# input_filter.net
KiCad netlist of a schematic drawn in Altium Designer
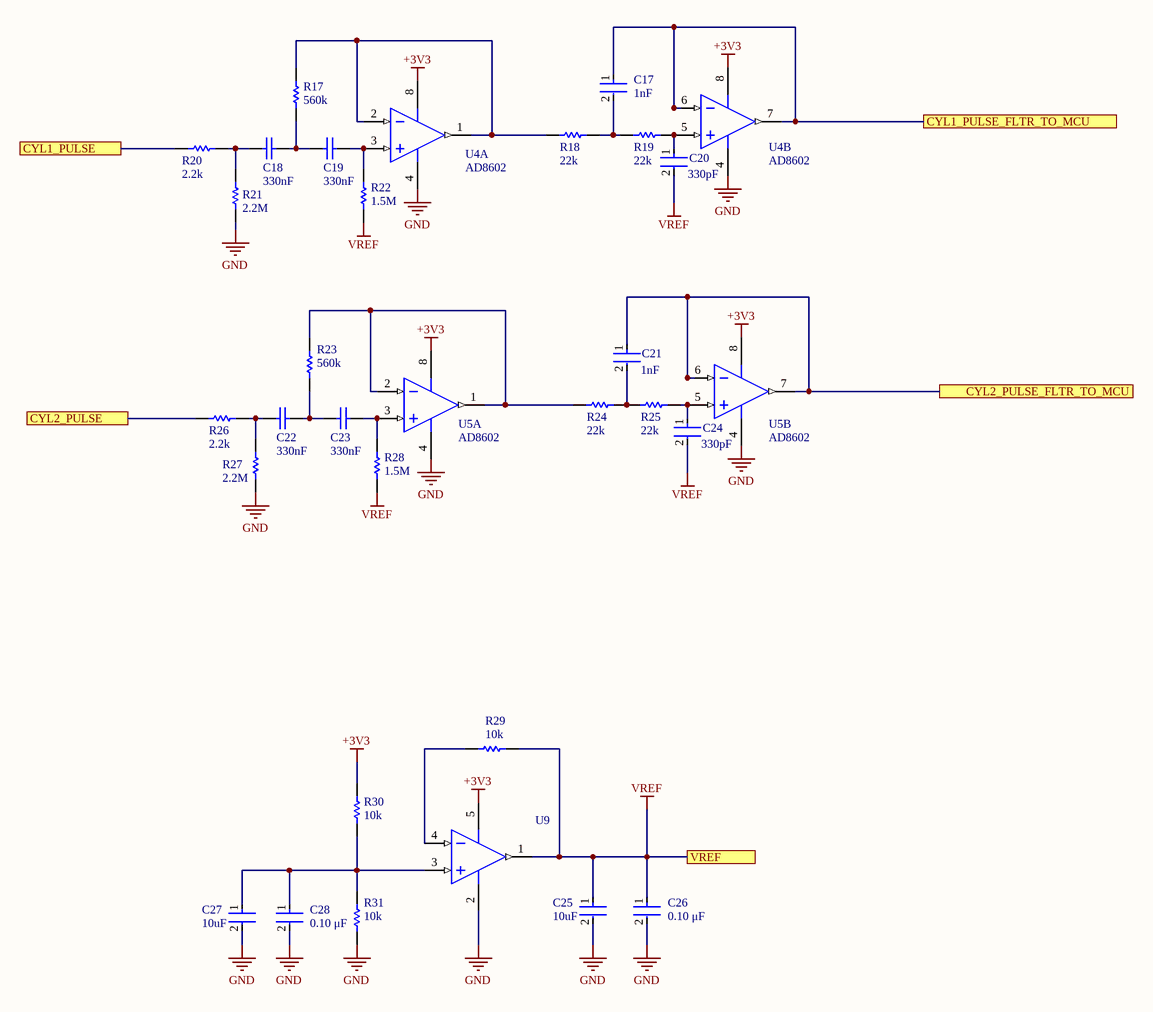
[diagram p0: input_filter.SchDoc]

(export (version "E")
  (design (tool "Eeschema 10.0.6"))
  (components
    (comp (ref "C17")
      (value "GRM1555C1H102JA01D")
      (footprint "FP-GRM155-0_05-IPC_B")
      (description "Chip Multilayer Ceramic Capacitors for General Purpose, 0402, 1000pF, C0G, 30ppm/°C, 5%, 50V")
      (fields
        (field (name "TOLERANCE") "5%")
        (field (name "VOLTAGE") "50V")
        (field (name "CAPACITANCE") "1nF")
      )
      (libsource (lib "Altium Content Vault") (part "02cd4be3c70576c341d710602a673aa"))
    )
    (comp (ref "C18")
      (value "330nF")
      (footprint "CAPC1005X55X25ML05T10")
      (fields (field (name "PART NUMBER") "GRM155R61A334KE15D") (field (name "MANUFACTURER") "Murata"))
      (libsource (lib "Altium Content Vault") (part "CAP"))
    )
    (comp (ref "C19")
      (value "330nF")
      (footprint "CAPC1005X55X25ML05T10")
      (fields (field (name "PART NUMBER") "GRM155R61A334KE15D") (field (name "MANUFACTURER") "Murata"))
      (libsource (lib "Altium Content Vault") (part "CAP"))
    )
    (comp (ref "C20")
      (value "GRM1555C1H331JA01D")
      (footprint "FP-GRM155-0_05-MFG")
      (description "Chip Multilayer Ceramic Capacitors for General Purpose, 0402, 330pF, C0G, 30ppm/°C, 5%, 50V")
      (fields
        (field (name "TOLERANCE") "5%")
        (field (name "VOLTAGE") "50V")
        (field (name "CAPACITANCE") "330pF")
      )
      (libsource (lib "Altium Content Vault") (part "02cd4be3c70576c341d710602a673aa"))
    )
    (comp (ref "C21")
      (value "GRM1555C1H102JA01D")
      (footprint "FP-GRM155-0_05-IPC_B")
      (description "Chip Multilayer Ceramic Capacitors for General Purpose, 0402, 1000pF, C0G, 30ppm/°C, 5%, 50V")
      (fields
        (field (name "TOLERANCE") "5%")
        (field (name "VOLTAGE") "50V")
        (field (name "CAPACITANCE") "1nF")
      )
      (libsource (lib "Altium Content Vault") (part "02cd4be3c70576c341d710602a673aa"))
    )
    (comp (ref "C22")
      (value "330nF")
      (footprint "CAPC1005X55X25ML05T10")
      (fields (field (name "PART NUMBER") "GRM155R61A334KE15D") (field (name "MANUFACTURER") "Murata"))
      (libsource (lib "Altium Content Vault") (part "CAP"))
    )
    (comp (ref "C23")
      (value "330nF")
      (footprint "CAPC1005X55X25ML05T10")
      (fields (field (name "PART NUMBER") "GRM155R61A334KE15D") (field (name "MANUFACTURER") "Murata"))
      (libsource (lib "Altium Content Vault") (part "CAP"))
    )
    (comp (ref "C24")
      (value "GRM1555C1H331JA01D")
      (footprint "FP-GRM155-0_05-MFG")
      (description "Chip Multilayer Ceramic Capacitors for General Purpose, 0402, 330pF, C0G, 30ppm/°C, 5%, 50V")
      (fields
        (field (name "TOLERANCE") "5%")
        (field (name "VOLTAGE") "50V")
        (field (name "CAPACITANCE") "330pF")
      )
      (libsource (lib "Altium Content Vault") (part "02cd4be3c70576c341d710602a673aa"))
    )
    (comp (ref "C25")
      (value "CL05A106MP5NUNC")
      (footprint "FP-CL05A106MP5NUNC-MFG")
      (description "CAP CER 10UF 10V X5R 0402")
      (fields
        (field (name "OCTOPART") "https://octopart.com/cl05a106mp5nunc-samsung-22457395")
        (field (name "TOLERANCE") "20%")
        (field (name "CAPACITANCE") "10uF")
      )
      (libsource (lib "Altium Content Vault") (part "b4654b650e69147ec39a6b967a45e02"))
    )
    (comp (ref "C26")
      (value "C0402C104K8PACTU")
      (footprint "FP-C0402-BB-MFG")
      (description "CAP CER 0.1UF 10V X5R 0402")
      (fields
        (field (name "CAPACITANCE") "0.10 μF")
        (field (name "MANUFACTURER") "Kemet")
        (field (name "TOLERANCE") "0.1")
      )
      (libsource (lib "Altium Content Vault") (part "b4654b650e69147ec39a6b967a45e02"))
    )
    (comp (ref "C27")
      (value "CL05A106MP5NUNC")
      (footprint "FP-CL05A106MP5NUNC-MFG")
      (description "CAP CER 10UF 10V X5R 0402")
      (fields
        (field (name "OCTOPART") "https://octopart.com/cl05a106mp5nunc-samsung-22457395")
        (field (name "TOLERANCE") "20%")
        (field (name "CAPACITANCE") "10uF")
      )
      (libsource (lib "Altium Content Vault") (part "b4654b650e69147ec39a6b967a45e02"))
    )
    (comp (ref "C28")
      (value "0.10 μF")
      (footprint "FP-C0402-BB-MFG")
      (description "CAP CER 0.1UF 10V X5R 0402")
      (fields (field (name "MANUFACTURER") "Kemet") (field (name "TOLERANCE") "0.1"))
      (libsource (lib "Altium Content Vault") (part "b4654b650e69147ec39a6b967a45e02"))
    )
    (comp (ref "R17")
      (value "560k")
      (footprint "RESC1005X40X25LL05T10")
      (fields (field (name "PART NUMBER") "RC0402FR-07560KL") (field (name "MANUFACTURER") "Yageo / Phycomp"))
      (libsource (lib "Altium Content Vault") (part "RES"))
    )
    (comp (ref "R18")
      (value "22k")
      (footprint "RESC1005X40X25NL05T10")
      (fields (field (name "MANUFACTURER") "Yageo / Phycomp") (field (name "PART NUMBER") "RC0402FR-0722KL"))
      (libsource (lib "Altium Content Vault") (part "RES"))
    )
    (comp (ref "R19")
      (value "22k")
      (footprint "RESC1005X40X25NL05T10")
      (fields (field (name "MANUFACTURER") "Yageo / Phycomp") (field (name "PART NUMBER") "RC0402FR-0722KL"))
      (libsource (lib "Altium Content Vault") (part "RES"))
    )
    (comp (ref "R20")
      (value "2.2k")
      (footprint "RESC1005X40X25NL05T10")
      (fields (field (name "MANUFACTURER") "Yageo / Phycomp") (field (name "PART NUMBER") "RC0402FR-0722KL"))
      (libsource (lib "Altium Content Vault") (part "RES"))
    )
    (comp (ref "R21")
      (value "2.2M")
      (footprint "RESC1005X40X25ML05T10")
      (fields (field (name "PART NUMBER") "RC0402FR-072M2L") (field (name "MANUFACTURER") "Yageo / Phycomp"))
      (libsource (lib "Altium Content Vault") (part "RES"))
    )
    (comp (ref "R22")
      (value "1.5M")
      (footprint "RESC1005X40X25NL05T10")
      (fields (field (name "MANUFACTURER") "Yageo / Phycomp") (field (name "PART NUMBER") "RC0402FR-071M5L"))
      (libsource (lib "Altium Content Vault") (part "RES"))
    )
    (comp (ref "R23")
      (value "560k")
      (footprint "RESC1005X40X25LL05T10")
      (fields (field (name "PART NUMBER") "RC0402FR-07560KL") (field (name "MANUFACTURER") "Yageo / Phycomp"))
      (libsource (lib "Altium Content Vault") (part "RES"))
    )
    (comp (ref "R24")
      (value "22k")
      (footprint "RESC1005X40X25NL05T10")
      (fields (field (name "MANUFACTURER") "Yageo / Phycomp") (field (name "PART NUMBER") "RC0402FR-0722KL"))
      (libsource (lib "Altium Content Vault") (part "RES"))
    )
    (comp (ref "R25")
      (value "22k")
      (footprint "RESC1005X40X25NL05T10")
      (fields (field (name "MANUFACTURER") "Yageo / Phycomp") (field (name "PART NUMBER") "RC0402FR-0722KL"))
      (libsource (lib "Altium Content Vault") (part "RES"))
    )
    (comp (ref "R26")
      (value "2.2k")
      (footprint "RESC1005X40X25NL05T10")
      (fields (field (name "MANUFACTURER") "Yageo / Phycomp") (field (name "PART NUMBER") "RC0402FR-0722KL"))
      (libsource (lib "Altium Content Vault") (part "RES"))
    )
    (comp (ref "R27")
      (value "2.2M")
      (footprint "RESC1005X40X25ML05T10")
      (fields (field (name "PART NUMBER") "RC0402FR-072M2L") (field (name "MANUFACTURER") "Yageo / Phycomp"))
      (libsource (lib "Altium Content Vault") (part "RES"))
    )
    (comp (ref "R28")
      (value "1.5M")
      (footprint "RESC1005X40X25NL05T10")
      (fields (field (name "MANUFACTURER") "Yageo / Phycomp") (field (name "PART NUMBER") "RC0402FR-071M5L"))
      (libsource (lib "Altium Content Vault") (part "RES"))
    )
    (comp (ref "R29")
      (value "10k")
      (footprint "RESC1005X40X25LL05T10")
      (fields (field (name "PART NUMBER") "RC0402FR-0710KL") (field (name "MANUFACTURER") "Yageo / Phycomp"))
      (libsource (lib "Altium Content Vault") (part "RES"))
    )
    (comp (ref "R30")
      (value "10k")
      (footprint "RESC1005X40X25LL05T10")
      (fields (field (name "PART NUMBER") "RC0402FR-0710KL") (field (name "MANUFACTURER") "Yageo / Phycomp"))
      (libsource (lib "Altium Content Vault") (part "RES"))
    )
    (comp (ref "R31")
      (value "10k")
      (footprint "RESC1005X40X25LL05T10")
      (fields (field (name "PART NUMBER") "RC0402FR-0710KL") (field (name "MANUFACTURER") "Yageo / Phycomp"))
      (libsource (lib "Altium Content Vault") (part "RES"))
    )
    (comp (ref "U4")
      (value "AD8602DRM-REEL")
      (footprint "ADI-RM-8_M")
      (fields (field (name "MANUFACTURER") "Analog Devices") (field (name "GENERIC PART NUMBER") "AD8602"))
      (libsource (lib "Altium Content Vault") (part "ADI-OP29X-R-8"))
    )
    (comp (ref "U5")
      (value "AD8602DRM-REEL")
      (footprint "ADI-RM-8_M")
      (fields (field (name "MANUFACTURER") "Analog Devices") (field (name "GENERIC PART NUMBER") "AD8602"))
      (libsource (lib "Altium Content Vault") (part "ADI-OP29X-R-8"))
    )
    (comp (ref "U9")
      (value "AD8031ARTZ-REEL7")
      (footprint "ADI-RJ-5_L")
      (fields (field (name "MANUFACTURER") "Analog Devices") (field (name "GENERIC PART NUMBER") "AD8031"))
      (libsource (lib "Altium Content Vault") (part "ADI-AD80XX-5"))
    )
  )
  (nets
    (net (code "1") (name "+3V3") (class "Default")
      (node (ref "R30") (pin "1") (pinfunction "1_1") (pintype "passive"))
      (node (ref "U4") (pin "8") (pinfunction "+V_8") (pintype "power_in"))
      (node (ref "U5") (pin "8") (pinfunction "+V_8") (pintype "power_in"))
      (node (ref "U9") (pin "5") (pinfunction "+VS_5") (pintype "power_in"))
    )
    (net (code "2") (name "/CYL1_PULSE") (class "Default")
      (node (ref "R20") (pin "1") (pinfunction "1_1") (pintype "passive"))
    )
    (net (code "3") (name "/CYL1_PULSE_FLTR_TO_MCU") (class "Default")
      (node (ref "C17") (pin "1") (pinfunction "1_1") (pintype "passive"))
      (node (ref "U4") (pin "6") (pinfunction "-IN_B_6") (pintype "input"))
      (node (ref "U4") (pin "7") (pinfunction "OUT_B_7") (pintype "output"))
    )
    (net (code "4") (name "/CYL2_PULSE") (class "Default")
      (node (ref "R26") (pin "1") (pinfunction "1_1") (pintype "passive"))
    )
    (net (code "5") (name "/CYL2_PULSE_FLTR_TO_MCU") (class "Default")
      (node (ref "C21") (pin "1") (pinfunction "1_1") (pintype "passive"))
      (node (ref "U5") (pin "6") (pinfunction "-IN_B_6") (pintype "input"))
      (node (ref "U5") (pin "7") (pinfunction "OUT_B_7") (pintype "output"))
    )
    (net (code "6") (name "GND") (class "Default")
      (node (ref "C25") (pin "2") (pinfunction "2_2") (pintype "passive"))
      (node (ref "C26") (pin "2") (pinfunction "2_2") (pintype "passive"))
      (node (ref "C27") (pin "2") (pinfunction "2_2") (pintype "passive"))
      (node (ref "C28") (pin "2") (pinfunction "2_2") (pintype "passive"))
      (node (ref "R21") (pin "1") (pinfunction "1_1") (pintype "passive"))
      (node (ref "R27") (pin "1") (pinfunction "1_1") (pintype "passive"))
      (node (ref "R31") (pin "2") (pinfunction "2_2") (pintype "passive"))
      (node (ref "U4") (pin "4") (pinfunction "-V_4") (pintype "power_in"))
      (node (ref "U5") (pin "4") (pinfunction "-V_4") (pintype "power_in"))
      (node (ref "U9") (pin "2") (pinfunction "-VS_2") (pintype "power_in"))
    )
    (net (code "7") (name "Net-(C17-Pad2)") (class "Default")
      (node (ref "C17") (pin "2") (pinfunction "2_2") (pintype "passive"))
      (node (ref "R18") (pin "2") (pinfunction "2_2") (pintype "passive"))
      (node (ref "R19") (pin "1") (pinfunction "1_1") (pintype "passive"))
    )
    (net (code "8") (name "Net-(C18-Pad1)") (class "Default")
      (node (ref "C18") (pin "1") (pinfunction "1_1") (pintype "passive"))
      (node (ref "R20") (pin "2") (pinfunction "2_2") (pintype "passive"))
      (node (ref "R21") (pin "2") (pinfunction "2_2") (pintype "passive"))
    )
    (net (code "9") (name "Net-(C18-Pad2)") (class "Default")
      (node (ref "C18") (pin "2") (pinfunction "2_2") (pintype "passive"))
      (node (ref "C19") (pin "1") (pinfunction "1_1") (pintype "passive"))
      (node (ref "R17") (pin "1") (pinfunction "1_1") (pintype "passive"))
    )
    (net (code "10") (name "Net-(C21-Pad2)") (class "Default")
      (node (ref "C21") (pin "2") (pinfunction "2_2") (pintype "passive"))
      (node (ref "R24") (pin "2") (pinfunction "2_2") (pintype "passive"))
      (node (ref "R25") (pin "1") (pinfunction "1_1") (pintype "passive"))
    )
    (net (code "11") (name "Net-(C22-Pad1)") (class "Default")
      (node (ref "C22") (pin "1") (pinfunction "1_1") (pintype "passive"))
      (node (ref "R26") (pin "2") (pinfunction "2_2") (pintype "passive"))
      (node (ref "R27") (pin "2") (pinfunction "2_2") (pintype "passive"))
    )
    (net (code "12") (name "Net-(C22-Pad2)") (class "Default")
      (node (ref "C22") (pin "2") (pinfunction "2_2") (pintype "passive"))
      (node (ref "C23") (pin "1") (pinfunction "1_1") (pintype "passive"))
      (node (ref "R23") (pin "1") (pinfunction "1_1") (pintype "passive"))
    )
    (net (code "13") (name "Net-(U4A-+IN_A)") (class "Default")
      (node (ref "C19") (pin "2") (pinfunction "2_2") (pintype "passive"))
      (node (ref "R22") (pin "2") (pinfunction "2_2") (pintype "passive"))
      (node (ref "U4") (pin "3") (pinfunction "+IN_A_3") (pintype "input"))
    )
    (net (code "14") (name "Net-(U4A--IN_A)") (class "Default")
      (node (ref "R17") (pin "2") (pinfunction "2_2") (pintype "passive"))
      (node (ref "R18") (pin "1") (pinfunction "1_1") (pintype "passive"))
      (node (ref "U4") (pin "1") (pinfunction "OUT_A_1") (pintype "output"))
      (node (ref "U4") (pin "2") (pinfunction "-IN_A_2") (pintype "input"))
    )
    (net (code "15") (name "Net-(U4B-+IN_B)") (class "Default")
      (node (ref "C20") (pin "1") (pinfunction "1_1") (pintype "passive"))
      (node (ref "R19") (pin "2") (pinfunction "2_2") (pintype "passive"))
      (node (ref "U4") (pin "5") (pinfunction "+IN_B_5") (pintype "input"))
    )
    (net (code "16") (name "Net-(U5A-+IN_A)") (class "Default")
      (node (ref "C23") (pin "2") (pinfunction "2_2") (pintype "passive"))
      (node (ref "R28") (pin "2") (pinfunction "2_2") (pintype "passive"))
      (node (ref "U5") (pin "3") (pinfunction "+IN_A_3") (pintype "input"))
    )
    (net (code "17") (name "Net-(U5A--IN_A)") (class "Default")
      (node (ref "R23") (pin "2") (pinfunction "2_2") (pintype "passive"))
      (node (ref "R24") (pin "1") (pinfunction "1_1") (pintype "passive"))
      (node (ref "U5") (pin "1") (pinfunction "OUT_A_1") (pintype "output"))
      (node (ref "U5") (pin "2") (pinfunction "-IN_A_2") (pintype "input"))
    )
    (net (code "18") (name "Net-(U5B-+IN_B)") (class "Default")
      (node (ref "C24") (pin "1") (pinfunction "1_1") (pintype "passive"))
      (node (ref "R25") (pin "2") (pinfunction "2_2") (pintype "passive"))
      (node (ref "U5") (pin "5") (pinfunction "+IN_B_5") (pintype "input"))
    )
    (net (code "19") (name "Net-(U9-+IN)") (class "Default")
      (node (ref "C27") (pin "1") (pinfunction "1_1") (pintype "passive"))
      (node (ref "C28") (pin "1") (pinfunction "1_1") (pintype "passive"))
      (node (ref "R30") (pin "2") (pinfunction "2_2") (pintype "passive"))
      (node (ref "R31") (pin "1") (pinfunction "1_1") (pintype "passive"))
      (node (ref "U9") (pin "3") (pinfunction "+IN_3") (pintype "input"))
    )
    (net (code "20") (name "Net-(U9--IN)") (class "Default")
      (node (ref "R29") (pin "2") (pinfunction "2_2") (pintype "passive"))
      (node (ref "U9") (pin "4") (pinfunction "-IN_4") (pintype "input"))
    )
    (net (code "21") (name "VREF") (class "Default")
      (node (ref "C20") (pin "2") (pinfunction "2_2") (pintype "passive"))
      (node (ref "C24") (pin "2") (pinfunction "2_2") (pintype "passive"))
      (node (ref "C25") (pin "1") (pinfunction "1_1") (pintype "passive"))
      (node (ref "C26") (pin "1") (pinfunction "1_1") (pintype "passive"))
      (node (ref "R22") (pin "1") (pinfunction "1_1") (pintype "passive"))
      (node (ref "R28") (pin "1") (pinfunction "1_1") (pintype "passive"))
      (node (ref "R29") (pin "1") (pinfunction "1_1") (pintype "passive"))
      (node (ref "U9") (pin "1") (pinfunction "VOUT_1") (pintype "output"))
    )
  )
)
